# RS485_promini_connecter.net
KiCad netlist of a schematic drawn in Altium Designer
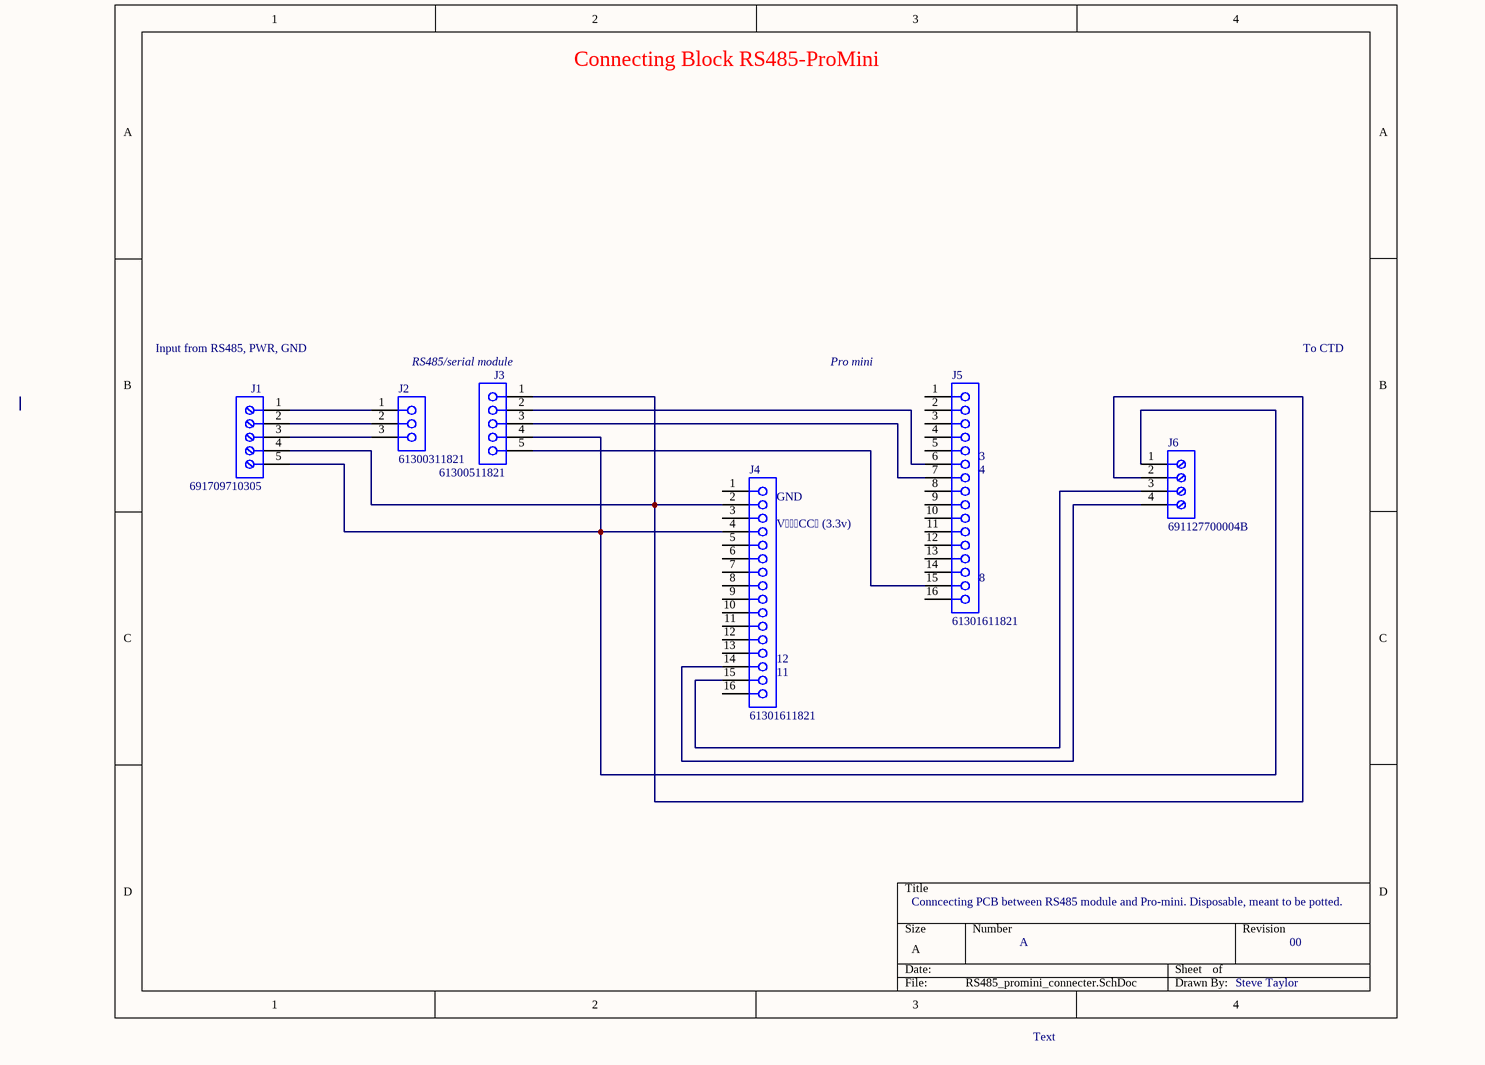
[diagram p0: RS485_promini_connecter.SchDoc]

(export (version "E")
  (design (tool "Eeschema 10.0.6"))
  (components
    (comp (ref "J1")
      (value "691709710305")
      (footprint "691709710305")
      (description "Terminal Block, 5.0MM, Rising Cage Clamp, Horizontal, SMT, 30-14 AWG, 5 Pins")
      (fields (field (name "VOLTAGE") "300V"))
      (libsource (lib "Altium Content Vault") (part "TBL - 1R - 05P - Screw"))
    )
    (comp (ref "J2")
      (value "61300311821")
      (footprint "61300311821")
      (description "Btb Conn, Rcpt, 3Pos, 1Row, 2.54Mm Rohs Compliant: Yes")
      (libsource (lib "Altium Content Vault") (part "Header_Female_1R_03P"))
    )
    (comp (ref "J3")
      (value "61300511821")
      (footprint "61300511821")
      (description "THT Vertical Socket Header WR-PHD, Pitch 2.54 mm, Single Row, 5 pins")
      (libsource (lib "Altium Content Vault") (part "Header_Female_1R_05P"))
    )
    (comp (ref "J4")
      (value "61301611821")
      (footprint "61301611821")
      (description "THT Vertical Socket Header WR-PHD, Pitch 2.54 mm, Single Row, 16 pins")
      (libsource (lib "Altium Content Vault") (part "Header_Female_1R_16P"))
    )
    (comp (ref "J5")
      (value "61301611821")
      (footprint "61301611821")
      (description "THT Vertical Socket Header WR-PHD, Pitch 2.54 mm, Single Row, 16 pins")
      (libsource (lib "Altium Content Vault") (part "Header_Female_1R_16P"))
    )
    (comp (ref "J6")
      (value "691127700004B")
      (footprint "691127700004B")
      (description "Terminal Block, 5MM Pitch, Vertical, Pressure Clamp, 30 to 12 AWG, 4 Pins, Grn")
      (fields (field (name "VOLTAGE") "300V"))
      (libsource (lib "Altium Content Vault") (part "TBL - 1R - 04P - Screw"))
    )
  )
  (nets
    (net (code "1") (name "Net-(J1-Pad1)") (class "Default")
      (node (ref "J1") (pin "1") (pinfunction "1_1") (pintype "passive"))
      (node (ref "J2") (pin "1") (pinfunction "1_1") (pintype "passive"))
    )
    (net (code "2") (name "Net-(J1-Pad2)") (class "Default")
      (node (ref "J1") (pin "2") (pinfunction "2_2") (pintype "passive"))
      (node (ref "J2") (pin "2") (pinfunction "2_2") (pintype "passive"))
    )
    (net (code "3") (name "Net-(J1-Pad3)") (class "Default")
      (node (ref "J1") (pin "3") (pinfunction "3_3") (pintype "passive"))
      (node (ref "J2") (pin "3") (pinfunction "3_3") (pintype "passive"))
    )
    (net (code "4") (name "Net-(J1-Pad4)") (class "Default")
      (node (ref "J1") (pin "4") (pinfunction "4_4") (pintype "passive"))
      (node (ref "J3") (pin "1") (pinfunction "1_1") (pintype "passive"))
      (node (ref "J4") (pin "2") (pinfunction "2_2") (pintype "passive"))
      (node (ref "J6") (pin "2") (pinfunction "2_2") (pintype "passive"))
    )
    (net (code "5") (name "Net-(J1-Pad5)") (class "Default")
      (node (ref "J1") (pin "5") (pinfunction "5_5") (pintype "passive"))
      (node (ref "J3") (pin "4") (pinfunction "4_4") (pintype "passive"))
      (node (ref "J4") (pin "4") (pinfunction "4_4") (pintype "passive"))
      (node (ref "J6") (pin "1") (pinfunction "1_1") (pintype "passive"))
    )
    (net (code "6") (name "Net-(J3-Pad2)") (class "Default")
      (node (ref "J3") (pin "2") (pinfunction "2_2") (pintype "passive"))
      (node (ref "J5") (pin "6") (pinfunction "6_6") (pintype "passive"))
    )
    (net (code "7") (name "Net-(J3-Pad3)") (class "Default")
      (node (ref "J3") (pin "3") (pinfunction "3_3") (pintype "passive"))
      (node (ref "J5") (pin "7") (pinfunction "7_7") (pintype "passive"))
    )
    (net (code "8") (name "Net-(J3-Pad5)") (class "Default")
      (node (ref "J3") (pin "5") (pinfunction "5_5") (pintype "passive"))
      (node (ref "J5") (pin "15") (pinfunction "15_15") (pintype "passive"))
    )
    (net (code "9") (name "Net-(J4-Pad14)") (class "Default")
      (node (ref "J4") (pin "14") (pinfunction "14_14") (pintype "passive"))
      (node (ref "J6") (pin "4") (pinfunction "4_4") (pintype "passive"))
    )
    (net (code "10") (name "Net-(J4-Pad15)") (class "Default")
      (node (ref "J4") (pin "15") (pinfunction "15_15") (pintype "passive"))
      (node (ref "J6") (pin "3") (pinfunction "3_3") (pintype "passive"))
    )
    (net (code "11") (name "unconnected-(J4-Pad1)") (class "Default")
      (node (ref "J4") (pin "1") (pinfunction "1_1") (pintype "passive"))
    )
    (net (code "12") (name "unconnected-(J4-Pad3)") (class "Default")
      (node (ref "J4") (pin "3") (pinfunction "3_3") (pintype "passive"))
    )
    (net (code "13") (name "unconnected-(J4-Pad5)") (class "Default")
      (node (ref "J4") (pin "5") (pinfunction "5_5") (pintype "passive"))
    )
    (net (code "14") (name "unconnected-(J4-Pad6)") (class "Default")
      (node (ref "J4") (pin "6") (pinfunction "6_6") (pintype "passive"))
    )
    (net (code "15") (name "unconnected-(J4-Pad7)") (class "Default")
      (node (ref "J4") (pin "7") (pinfunction "7_7") (pintype "passive"))
    )
    (net (code "16") (name "unconnected-(J4-Pad8)") (class "Default")
      (node (ref "J4") (pin "8") (pinfunction "8_8") (pintype "passive"))
    )
    (net (code "17") (name "unconnected-(J4-Pad9)") (class "Default")
      (node (ref "J4") (pin "9") (pinfunction "9_9") (pintype "passive"))
    )
    (net (code "18") (name "unconnected-(J4-Pad10)") (class "Default")
      (node (ref "J4") (pin "10") (pinfunction "10_10") (pintype "passive"))
    )
    (net (code "19") (name "unconnected-(J4-Pad11)") (class "Default")
      (node (ref "J4") (pin "11") (pinfunction "11_11") (pintype "passive"))
    )
    (net (code "20") (name "unconnected-(J4-Pad12)") (class "Default")
      (node (ref "J4") (pin "12") (pinfunction "12_12") (pintype "passive"))
    )
    (net (code "21") (name "unconnected-(J4-Pad13)") (class "Default")
      (node (ref "J4") (pin "13") (pinfunction "13_13") (pintype "passive"))
    )
    (net (code "22") (name "unconnected-(J4-Pad16)") (class "Default")
      (node (ref "J4") (pin "16") (pinfunction "16_16") (pintype "passive"))
    )
    (net (code "23") (name "unconnected-(J5-Pad1)") (class "Default")
      (node (ref "J5") (pin "1") (pinfunction "1_1") (pintype "passive"))
    )
    (net (code "24") (name "unconnected-(J5-Pad2)") (class "Default")
      (node (ref "J5") (pin "2") (pinfunction "2_2") (pintype "passive"))
    )
    (net (code "25") (name "unconnected-(J5-Pad3)") (class "Default")
      (node (ref "J5") (pin "3") (pinfunction "3_3") (pintype "passive"))
    )
    (net (code "26") (name "unconnected-(J5-Pad4)") (class "Default")
      (node (ref "J5") (pin "4") (pinfunction "4_4") (pintype "passive"))
    )
    (net (code "27") (name "unconnected-(J5-Pad5)") (class "Default")
      (node (ref "J5") (pin "5") (pinfunction "5_5") (pintype "passive"))
    )
    (net (code "28") (name "unconnected-(J5-Pad8)") (class "Default")
      (node (ref "J5") (pin "8") (pinfunction "8_8") (pintype "passive"))
    )
    (net (code "29") (name "unconnected-(J5-Pad9)") (class "Default")
      (node (ref "J5") (pin "9") (pinfunction "9_9") (pintype "passive"))
    )
    (net (code "30") (name "unconnected-(J5-Pad10)") (class "Default")
      (node (ref "J5") (pin "10") (pinfunction "10_10") (pintype "passive"))
    )
    (net (code "31") (name "unconnected-(J5-Pad11)") (class "Default")
      (node (ref "J5") (pin "11") (pinfunction "11_11") (pintype "passive"))
    )
    (net (code "32") (name "unconnected-(J5-Pad12)") (class "Default")
      (node (ref "J5") (pin "12") (pinfunction "12_12") (pintype "passive"))
    )
    (net (code "33") (name "unconnected-(J5-Pad13)") (class "Default")
      (node (ref "J5") (pin "13") (pinfunction "13_13") (pintype "passive"))
    )
    (net (code "34") (name "unconnected-(J5-Pad14)") (class "Default")
      (node (ref "J5") (pin "14") (pinfunction "14_14") (pintype "passive"))
    )
    (net (code "35") (name "unconnected-(J5-Pad16)") (class "Default")
      (node (ref "J5") (pin "16") (pinfunction "16_16") (pintype "passive"))
    )
  )
)
